# hpma115c0-004_adapter.net
KiCad netlist of a schematic drawn in EAGLE
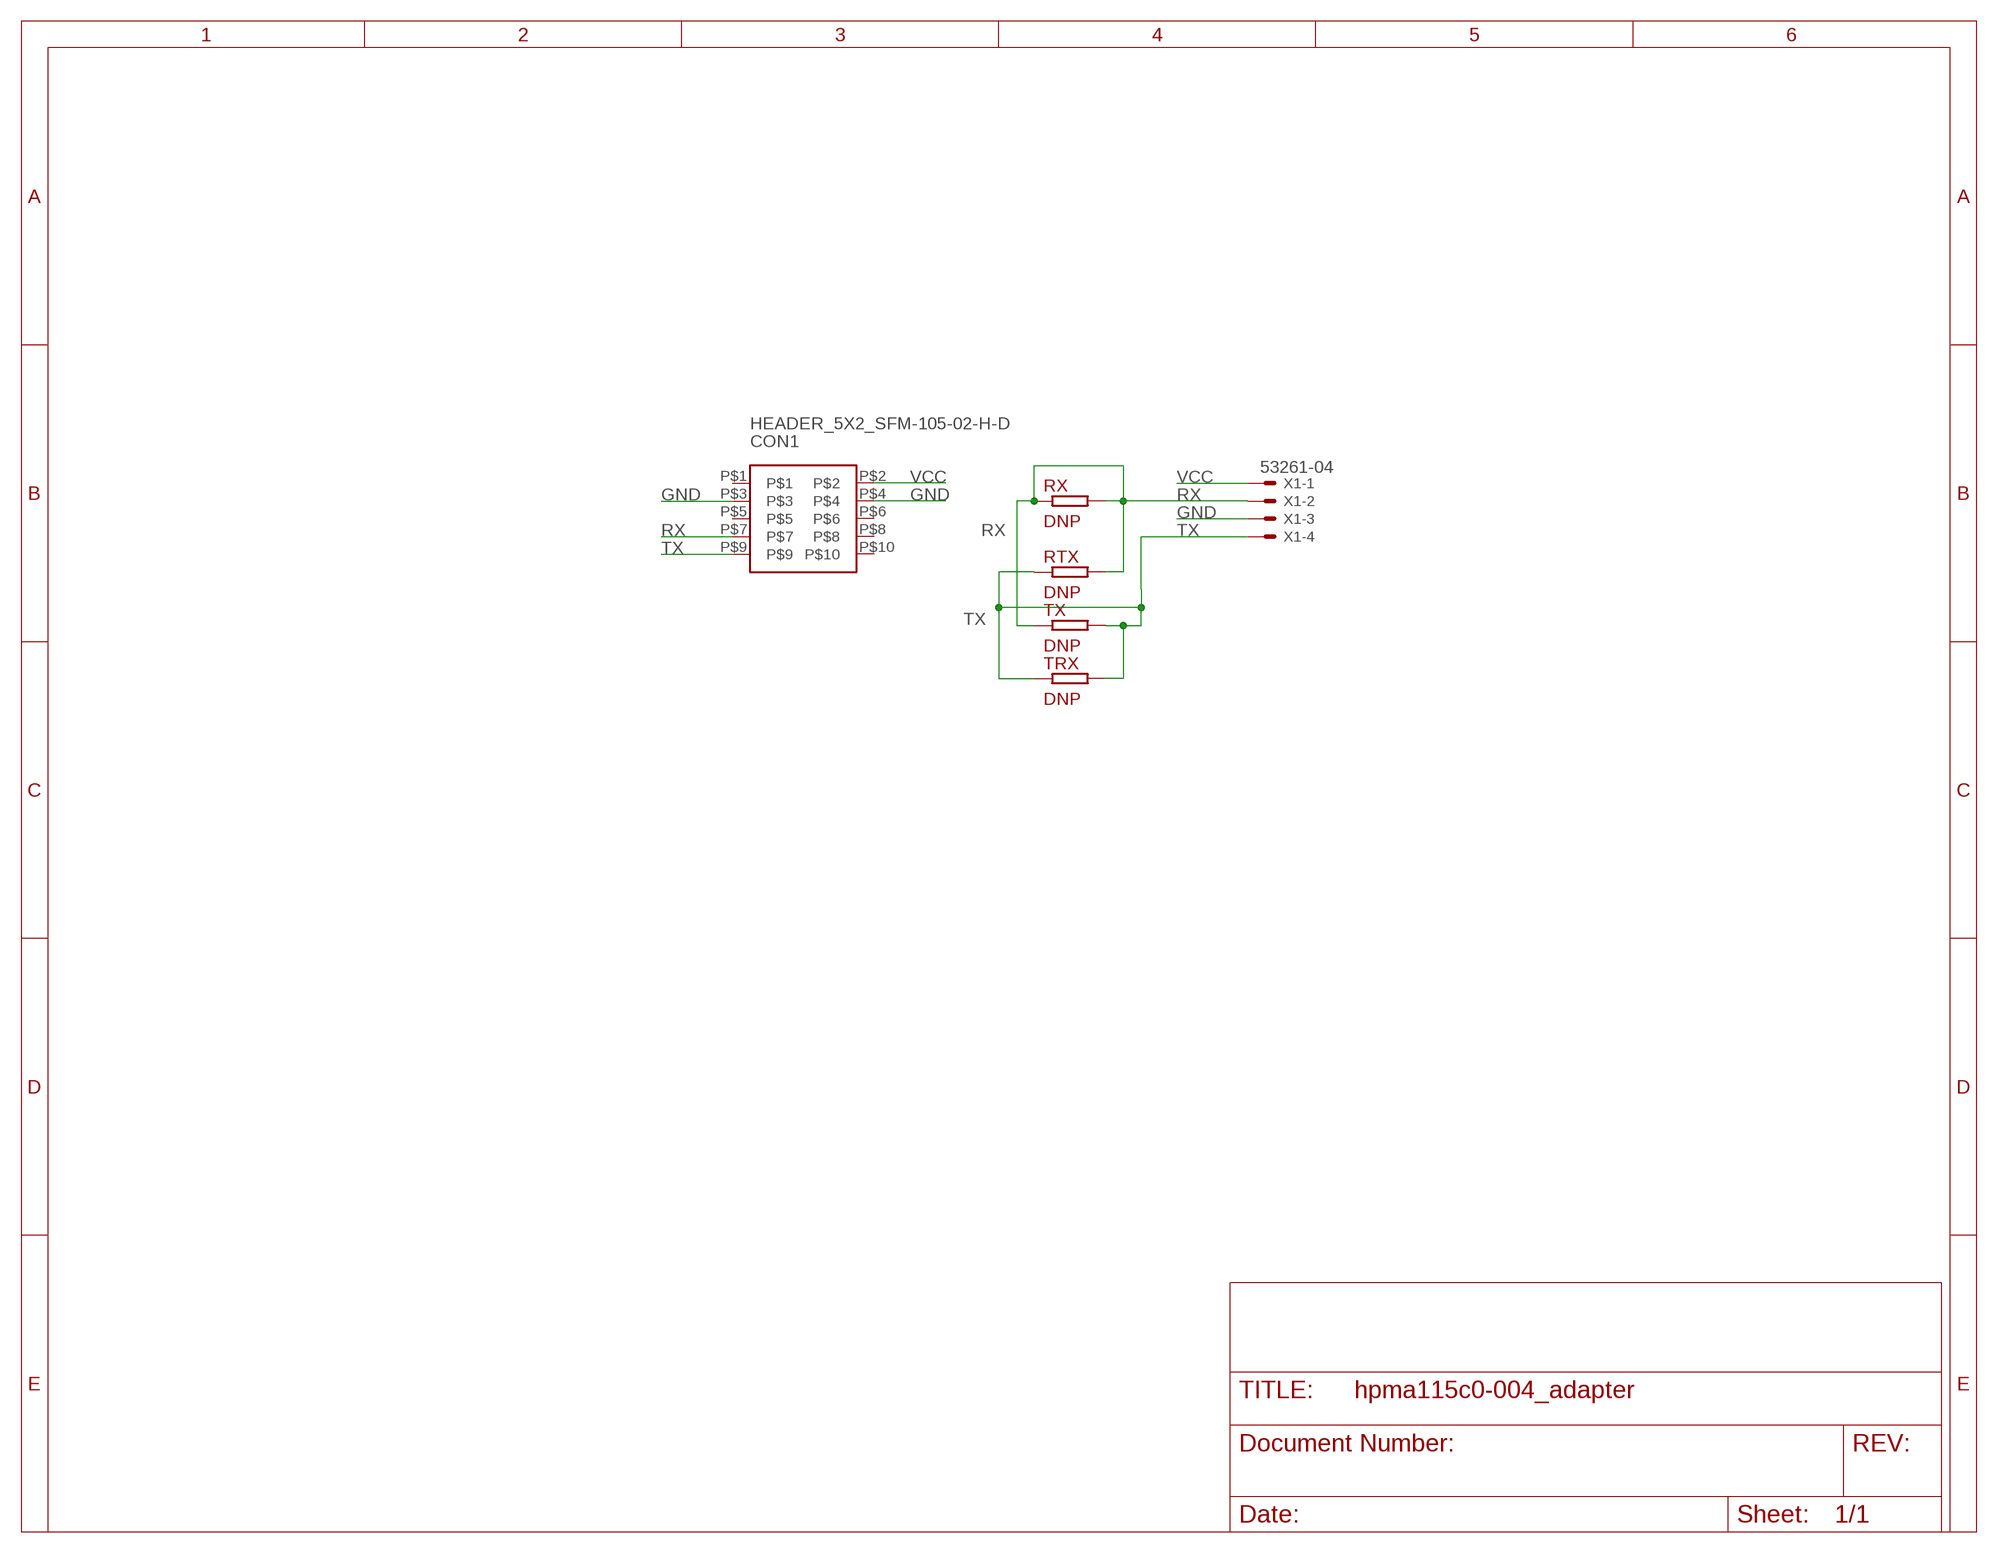
[diagram p0: schematic, sheet 1]

(export (version "E")
  (design (tool "Eeschema 10.0.6"))
  (components
    (comp (ref "CON1")
      (value "HEADER_5X2_SFM-105-02-H-D")
      (footprint "eagle-import:HEADER_5X2_1.27X1.27_SMD_SAMTEK")
      (libsource (lib "eagle-import") (part "HEADER_5X2_SFM-105-02-H-D"))
    )
    (comp (ref "RTX")
      (value "DNP")
      (footprint "eagle-import:SMD_0402")
      (libsource (lib "eagle-import") (part "RESISTOR_0402"))
    )
    (comp (ref "RX")
      (value "DNP")
      (footprint "eagle-import:SMD_0402")
      (libsource (lib "eagle-import") (part "RESISTOR_0402"))
    )
    (comp (ref "TRX")
      (value "DNP")
      (footprint "eagle-import:SMD_0402")
      (libsource (lib "eagle-import") (part "RESISTOR_0402"))
    )
    (comp (ref "TX")
      (value "DNP")
      (footprint "eagle-import:SMD_0402")
      (libsource (lib "eagle-import") (part "RESISTOR_0402"))
    )
    (comp (ref "X1")
      (value "53261-04")
      (footprint "eagle-import:53261-04")
      (fields (field (name "MF") "MOLEX"))
      (libsource (lib "eagle-import") (part "53?-04261"))
    )
  )
  (nets
    (net (code "1") (name "/GND") (class "Default")
      (node (ref "CON1") (pin "P$3") (pinfunction "P$3_P$3") (pintype "bidirectional"))
      (node (ref "CON1") (pin "P$4") (pinfunction "P$4_P$4") (pintype "bidirectional"))
      (node (ref "X1") (pin "3") (pinfunction "S_3") (pintype "passive"))
    )
    (net (code "2") (name "/RX") (class "Default")
      (node (ref "CON1") (pin "P$7") (pinfunction "P$7_P$7") (pintype "bidirectional"))
      (node (ref "RTX") (pin "P$2") (pinfunction "P$2_P$2") (pintype "passive"))
      (node (ref "RX") (pin "P$1") (pinfunction "P$1_P$1") (pintype "passive"))
      (node (ref "RX") (pin "P$2") (pinfunction "P$2_P$2") (pintype "passive"))
      (node (ref "TX") (pin "P$1") (pinfunction "P$1_P$1") (pintype "passive"))
      (node (ref "X1") (pin "2") (pinfunction "S_2") (pintype "passive"))
    )
    (net (code "3") (name "/TX") (class "Default")
      (node (ref "CON1") (pin "P$9") (pinfunction "P$9_P$9") (pintype "bidirectional"))
      (node (ref "RTX") (pin "P$1") (pinfunction "P$1_P$1") (pintype "passive"))
      (node (ref "TRX") (pin "P$1") (pinfunction "P$1_P$1") (pintype "passive"))
      (node (ref "TRX") (pin "P$2") (pinfunction "P$2_P$2") (pintype "passive"))
      (node (ref "TX") (pin "P$2") (pinfunction "P$2_P$2") (pintype "passive"))
      (node (ref "X1") (pin "4") (pinfunction "S_4") (pintype "passive"))
    )
    (net (code "4") (name "/VCC") (class "Default")
      (node (ref "CON1") (pin "P$2") (pinfunction "P$2_P$2") (pintype "bidirectional"))
      (node (ref "X1") (pin "1") (pinfunction "S_1") (pintype "passive"))
    )
    (net (code "5") (name "unconnected-(CON1-PadP$1)") (class "Default")
      (node (ref "CON1") (pin "P$1") (pinfunction "P$1_P$1") (pintype "bidirectional"))
    )
    (net (code "6") (name "unconnected-(CON1-PadP$5)") (class "Default")
      (node (ref "CON1") (pin "P$5") (pinfunction "P$5_P$5") (pintype "bidirectional"))
    )
    (net (code "7") (name "unconnected-(CON1-PadP$6)") (class "Default")
      (node (ref "CON1") (pin "P$6") (pinfunction "P$6_P$6") (pintype "bidirectional"))
    )
    (net (code "8") (name "unconnected-(CON1-PadP$8)") (class "Default")
      (node (ref "CON1") (pin "P$8") (pinfunction "P$8_P$8") (pintype "bidirectional"))
    )
    (net (code "9") (name "unconnected-(CON1-PadP$10)") (class "Default")
      (node (ref "CON1") (pin "P$10") (pinfunction "P$10_P$10") (pintype "bidirectional"))
    )
  )
)
